# TM8_EVO_Dad.net
KiCad netlist of a schematic drawn in EAGLE
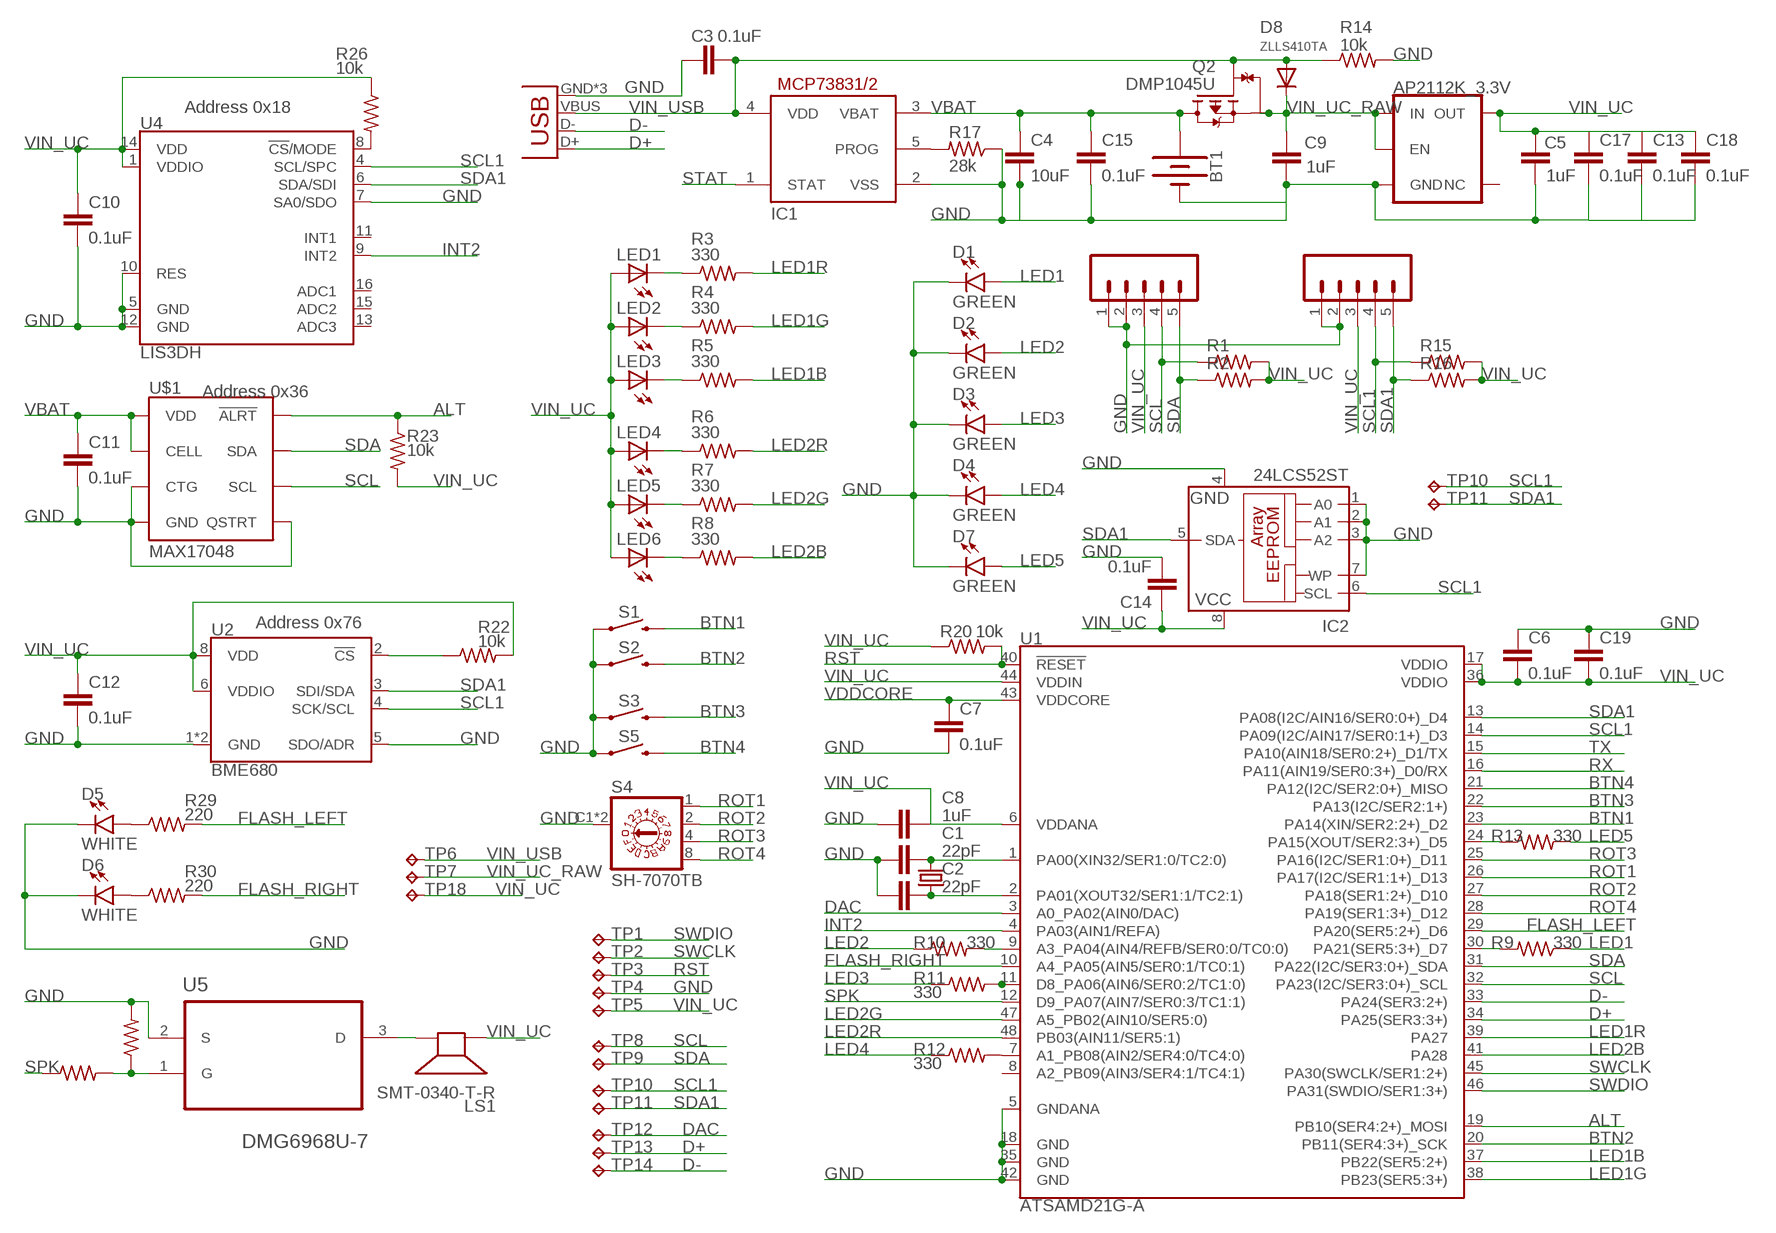
[diagram p0: schematic, sheet 1]

(export (version "E")
  (design (tool "Eeschema 10.0.6"))
  (components
    (comp (ref "AP2112K_3.3V")
      (value "3.3V")
      (footprint "eagle-import:SOT23-5")
      (libsource (lib "eagle-import") (part "V_REG_AP2112K-3.3V"))
    )
    (comp (ref "BT1")
      (value "BATTERY-20MM_SMD_4LEGS_OVERPASTE_INNER")
      (footprint "eagle-import:BATTCON_20MM_4LEGS_OVERPASTE_INNER")
      (libsource (lib "eagle-import") (part "BATTERY-20MM_SMD_4LEGS_OVERPASTE_INNER"))
    )
    (comp (ref "C1")
      (value "22pF")
      (footprint "eagle-import:C0402")
      (libsource (lib "eagle-import") (part "C-EUC0402"))
    )
    (comp (ref "C2")
      (value "22pF")
      (footprint "eagle-import:C0402")
      (libsource (lib "eagle-import") (part "C-EUC0402"))
    )
    (comp (ref "C3")
      (value "0.1uF")
      (footprint "eagle-import:C0402")
      (libsource (lib "eagle-import") (part "C-EUC0402"))
    )
    (comp (ref "C4")
      (value "10uF")
      (footprint "eagle-import:C0402")
      (libsource (lib "eagle-import") (part "C-EUC0402"))
    )
    (comp (ref "C5")
      (value "1uF")
      (footprint "eagle-import:C0402")
      (libsource (lib "eagle-import") (part "C-EUC0402"))
    )
    (comp (ref "C6")
      (value "0.1uF")
      (footprint "eagle-import:C0402")
      (libsource (lib "eagle-import") (part "C-EUC0402"))
    )
    (comp (ref "C7")
      (value "0.1uF")
      (footprint "eagle-import:C0402")
      (libsource (lib "eagle-import") (part "C-EUC0402"))
    )
    (comp (ref "C8")
      (value "1uF")
      (footprint "eagle-import:C0402")
      (libsource (lib "eagle-import") (part "C-EUC0402"))
    )
    (comp (ref "C9")
      (value "1uF")
      (footprint "eagle-import:C0402")
      (libsource (lib "eagle-import") (part "C-EUC0402"))
    )
    (comp (ref "C10")
      (value "0.1uF")
      (footprint "eagle-import:C0402")
      (libsource (lib "eagle-import") (part "C-EUC0402"))
    )
    (comp (ref "C11")
      (value "0.1uF")
      (footprint "eagle-import:C0402")
      (libsource (lib "eagle-import") (part "C-EUC0402"))
    )
    (comp (ref "C12")
      (value "0.1uF")
      (footprint "eagle-import:C0402")
      (libsource (lib "eagle-import") (part "C-EUC0402"))
    )
    (comp (ref "C13")
      (value "0.1uF")
      (footprint "eagle-import:C0402")
      (libsource (lib "eagle-import") (part "C-EUC0402"))
    )
    (comp (ref "C14")
      (value "0.1uF")
      (footprint "eagle-import:C0402")
      (libsource (lib "eagle-import") (part "C-EUC0402"))
    )
    (comp (ref "C15")
      (value "0.1uF")
      (footprint "eagle-import:C0402")
      (libsource (lib "eagle-import") (part "C-EUC0402"))
    )
    (comp (ref "C17")
      (value "0.1uF")
      (footprint "eagle-import:C0402")
      (libsource (lib "eagle-import") (part "C-EUC0402"))
    )
    (comp (ref "C18")
      (value "0.1uF")
      (footprint "eagle-import:C0402")
      (libsource (lib "eagle-import") (part "C-EUC0402"))
    )
    (comp (ref "C19")
      (value "0.1uF")
      (footprint "eagle-import:C0402")
      (libsource (lib "eagle-import") (part "C-EUC0402"))
    )
    (comp (ref "D1")
      (value "GREEN")
      (footprint "eagle-import:LED-1206")
      (libsource (lib "eagle-import") (part "LED-GREEN1206"))
    )
    (comp (ref "D2")
      (value "GREEN")
      (footprint "eagle-import:LED-1206")
      (libsource (lib "eagle-import") (part "LED-GREEN1206"))
    )
    (comp (ref "D3")
      (value "GREEN")
      (footprint "eagle-import:LED-1206")
      (libsource (lib "eagle-import") (part "LED-GREEN1206"))
    )
    (comp (ref "D4")
      (value "GREEN")
      (footprint "eagle-import:LED-1206")
      (libsource (lib "eagle-import") (part "LED-GREEN1206"))
    )
    (comp (ref "D5")
      (value "WHITE")
      (footprint "eagle-import:LED-1206")
      (libsource (lib "eagle-import") (part "LED-WHITE1206"))
    )
    (comp (ref "D6")
      (value "WHITE")
      (footprint "eagle-import:LED-1206")
      (libsource (lib "eagle-import") (part "LED-WHITE1206"))
    )
    (comp (ref "D7")
      (value "GREEN")
      (footprint "eagle-import:LED-1206")
      (libsource (lib "eagle-import") (part "LED-GREEN1206"))
    )
    (comp (ref "D8")
      (value "ZLLS410TA")
      (footprint "eagle-import:SOD-323F")
      (libsource (lib "eagle-import") (part "DIODESOD-323F"))
    )
    (comp (ref "IC1")
      (value "MCP73831/OT")
      (footprint "eagle-import:SOT23-5L")
      (libsource (lib "eagle-import") (part "MCP73831/OT"))
    )
    (comp (ref "IC2")
      (value "24LCS52ST")
      (footprint "eagle-import:TSSOP8")
      (fields (field (name "MF") "MICROCHIP") (field (name "MPN") "24LCS52T/ST"))
      (libsource (lib "eagle-import") (part "24STLCS52"))
    )
    (comp (ref "JP2")
      (value "USB-MICROB")
      (footprint "eagle-import:USB-MICROB")
      (libsource (lib "eagle-import") (part "USB-MICROB"))
    )
    (comp (ref "LCD1")
      (value "CONN_05VERT_FEMALE_HEADER")
      (footprint "eagle-import:1X05_SMD_VERTICAL_COMBO")
      (libsource (lib "eagle-import") (part "CONN_05VERT_FEMALE_HEADER"))
    )
    (comp (ref "LCD2")
      (value "CONN_05VERT_FEMALE_HEADER")
      (footprint "eagle-import:1X05_SMD_VERTICAL_COMBO")
      (libsource (lib "eagle-import") (part "CONN_05VERT_FEMALE_HEADER"))
    )
    (comp (ref "LED1")
      (value "LEDCHIPLED_0805")
      (footprint "eagle-import:CHIPLED_0805")
      (libsource (lib "eagle-import") (part "LEDCHIPLED_0805"))
    )
    (comp (ref "LED2")
      (value "LEDCHIPLED_0805")
      (footprint "eagle-import:CHIPLED_0805")
      (libsource (lib "eagle-import") (part "LEDCHIPLED_0805"))
    )
    (comp (ref "LED3")
      (value "LEDCHIPLED_0805")
      (footprint "eagle-import:CHIPLED_0805")
      (libsource (lib "eagle-import") (part "LEDCHIPLED_0805"))
    )
    (comp (ref "LED4")
      (value "LEDCHIPLED_0805")
      (footprint "eagle-import:CHIPLED_0805")
      (libsource (lib "eagle-import") (part "LEDCHIPLED_0805"))
    )
    (comp (ref "LED5")
      (value "LEDCHIPLED_0805")
      (footprint "eagle-import:CHIPLED_0805")
      (libsource (lib "eagle-import") (part "LEDCHIPLED_0805"))
    )
    (comp (ref "LED6")
      (value "LEDCHIPLED_0805")
      (footprint "eagle-import:CHIPLED_0805")
      (libsource (lib "eagle-import") (part "LEDCHIPLED_0805"))
    )
    (comp (ref "LS1")
      (value "SMT-0340-T-R")
      (footprint "eagle-import:XDCR_SMT-0340-T-R")
      (fields (field (name "MANUFACTURER") "Pui Audio"))
      (libsource (lib "eagle-import") (part "SMT-0340-T-R"))
    )
    (comp (ref "Q2")
      (value "DMP1045U")
      (footprint "eagle-import:SOT91P240X110-3N")
      (fields (field (name "MF") "Diodes Inc."))
      (libsource (lib "eagle-import") (part "DMP1045U"))
    )
    (comp (ref "R1")
      (value "R-US_R0402")
      (footprint "eagle-import:R0402")
      (libsource (lib "eagle-import") (part "adafruit_25768682_R-US_R0402"))
    )
    (comp (ref "R2")
      (value "R-US_R0402")
      (footprint "eagle-import:R0402")
      (libsource (lib "eagle-import") (part "adafruit_25768682_R-US_R0402"))
    )
    (comp (ref "R3")
      (value "330")
      (footprint "eagle-import:R0402")
      (libsource (lib "eagle-import") (part "rcl_334_R-US_R0402"))
    )
    (comp (ref "R4")
      (value "330")
      (footprint "eagle-import:R0402")
      (libsource (lib "eagle-import") (part "rcl_334_R-US_R0402"))
    )
    (comp (ref "R5")
      (value "330")
      (footprint "eagle-import:R0402")
      (libsource (lib "eagle-import") (part "rcl_334_R-US_R0402"))
    )
    (comp (ref "R6")
      (value "330")
      (footprint "eagle-import:R0402")
      (libsource (lib "eagle-import") (part "rcl_334_R-US_R0402"))
    )
    (comp (ref "R7")
      (value "330")
      (footprint "eagle-import:R0402")
      (libsource (lib "eagle-import") (part "rcl_334_R-US_R0402"))
    )
    (comp (ref "R8")
      (value "330")
      (footprint "eagle-import:R0402")
      (libsource (lib "eagle-import") (part "rcl_334_R-US_R0402"))
    )
    (comp (ref "R9")
      (value "330")
      (footprint "eagle-import:R0402")
      (libsource (lib "eagle-import") (part "rcl_334_R-US_R0402"))
    )
    (comp (ref "R10")
      (value "330")
      (footprint "eagle-import:R0402")
      (libsource (lib "eagle-import") (part "rcl_334_R-US_R0402"))
    )
    (comp (ref "R11")
      (value "330")
      (footprint "eagle-import:R0402")
      (libsource (lib "eagle-import") (part "rcl_334_R-US_R0402"))
    )
    (comp (ref "R12")
      (value "330")
      (footprint "eagle-import:R0402")
      (libsource (lib "eagle-import") (part "rcl_334_R-US_R0402"))
    )
    (comp (ref "R13")
      (value "330")
      (footprint "eagle-import:R0402")
      (libsource (lib "eagle-import") (part "rcl_334_R-US_R0402"))
    )
    (comp (ref "R14")
      (value "10k")
      (footprint "eagle-import:R0402")
      (libsource (lib "eagle-import") (part "R-US_R0402"))
    )
    (comp (ref "R15")
      (value "R-US_R0402")
      (footprint "eagle-import:R0402")
      (libsource (lib "eagle-import") (part "adafruit_25768682_R-US_R0402"))
    )
    (comp (ref "R16")
      (value "R-US_R0402")
      (footprint "eagle-import:R0402")
      (libsource (lib "eagle-import") (part "adafruit_25768682_R-US_R0402"))
    )
    (comp (ref "R17")
      (value "28k")
      (footprint "eagle-import:R0402")
      (libsource (lib "eagle-import") (part "adafruit_25768682_R-US_R0402"))
    )
    (comp (ref "R18")
      (value "220")
      (footprint "eagle-import:R0402")
      (libsource (lib "eagle-import") (part "rcl_334_R-US_R0402"))
    )
    (comp (ref "R19")
      (value "220")
      (footprint "eagle-import:R0402")
      (libsource (lib "eagle-import") (part "rcl_334_R-US_R0402"))
    )
    (comp (ref "R20")
      (value "10k")
      (footprint "eagle-import:R0402")
      (libsource (lib "eagle-import") (part "adafruit_25768682_R-US_R0402"))
    )
    (comp (ref "R22")
      (value "10k")
      (footprint "eagle-import:R0402")
      (libsource (lib "eagle-import") (part "rcl_334_R-US_R0402"))
    )
    (comp (ref "R23")
      (value "10k")
      (footprint "eagle-import:R0402")
      (libsource (lib "eagle-import") (part "rcl_334_R-US_R0402"))
    )
    (comp (ref "R26")
      (value "10k")
      (footprint "eagle-import:R0402")
      (libsource (lib "eagle-import") (part "rcl_334_R-US_R0402"))
    )
    (comp (ref "R29")
      (value "220")
      (footprint "eagle-import:R0402")
      (libsource (lib "eagle-import") (part "rcl_334_R-US_R0402"))
    )
    (comp (ref "R30")
      (value "220")
      (footprint "eagle-import:R0402")
      (libsource (lib "eagle-import") (part "rcl_334_R-US_R0402"))
    )
    (comp (ref "S1")
      (value "MOMENTARY-SWITCH-SPST-SMD-6.0X3.5MM")
      (footprint "eagle-import:TACTILE_SWITCH_SMD_6.0X3.5MM")
      (libsource (lib "eagle-import") (part "MOMENTARY-SWITCH-SPST-SMD-6.0X3.5MM"))
    )
    (comp (ref "S2")
      (value "MOMENTARY-SWITCH-SPST-SMD-6.0X3.5MM")
      (footprint "eagle-import:TACTILE_SWITCH_SMD_6.0X3.5MM")
      (libsource (lib "eagle-import") (part "MOMENTARY-SWITCH-SPST-SMD-6.0X3.5MM"))
    )
    (comp (ref "S3")
      (value "MOMENTARY-SWITCH-SPST-SMD-6.0X3.5MM")
      (footprint "eagle-import:TACTILE_SWITCH_SMD_6.0X3.5MM")
      (libsource (lib "eagle-import") (part "MOMENTARY-SWITCH-SPST-SMD-6.0X3.5MM"))
    )
    (comp (ref "S4")
      (value "SH-7070TB")
      (footprint "eagle-import:SH-7070B")
      (fields (field (name "MF") "Nidec Copal"))
      (libsource (lib "eagle-import") (part "SH-7070TB"))
    )
    (comp (ref "S5")
      (value "MOMENTARY-SWITCH-SPST-SMD-6.0X3.5MM")
      (footprint "eagle-import:TACTILE_SWITCH_SMD_6.0X3.5MM")
      (libsource (lib "eagle-import") (part "MOMENTARY-SWITCH-SPST-SMD-6.0X3.5MM"))
    )
    (comp (ref "TP1")
      (value "TPTP14R")
      (footprint "eagle-import:TP14R")
      (libsource (lib "eagle-import") (part "TPTP14R"))
    )
    (comp (ref "TP2")
      (value "TPTP14R")
      (footprint "eagle-import:TP14R")
      (libsource (lib "eagle-import") (part "TPTP14R"))
    )
    (comp (ref "TP3")
      (value "TPTP14R")
      (footprint "eagle-import:TP14R")
      (libsource (lib "eagle-import") (part "TPTP14R"))
    )
    (comp (ref "TP4")
      (value "TPTP14R")
      (footprint "eagle-import:TP14R")
      (libsource (lib "eagle-import") (part "TPTP14R"))
    )
    (comp (ref "TP5")
      (value "TPTP14R")
      (footprint "eagle-import:TP14R")
      (libsource (lib "eagle-import") (part "TPTP14R"))
    )
    (comp (ref "TP6")
      (value "TPTP14R")
      (footprint "eagle-import:TP14R")
      (libsource (lib "eagle-import") (part "TPTP14R"))
    )
    (comp (ref "TP7")
      (value "TPTP14R")
      (footprint "eagle-import:TP14R")
      (libsource (lib "eagle-import") (part "TPTP14R"))
    )
    (comp (ref "TP8")
      (value "TPTP14R")
      (footprint "eagle-import:TP14R")
      (libsource (lib "eagle-import") (part "TPTP14R"))
    )
    (comp (ref "TP9")
      (value "TPTP14R")
      (footprint "eagle-import:TP14R")
      (libsource (lib "eagle-import") (part "TPTP14R"))
    )
    (comp (ref "TP10")
      (value "TPTP14R")
      (footprint "eagle-import:TP14R")
      (libsource (lib "eagle-import") (part "TPTP14R"))
    )
    (comp (ref "TP11")
      (value "TPTP14R")
      (footprint "eagle-import:TP14R")
      (libsource (lib "eagle-import") (part "TPTP14R"))
    )
    (comp (ref "TP12")
      (value "TPTP14R")
      (footprint "eagle-import:TP14R")
      (libsource (lib "eagle-import") (part "TPTP14R"))
    )
    (comp (ref "TP13")
      (value "TPTP14R")
      (footprint "eagle-import:TP14R")
      (libsource (lib "eagle-import") (part "TPTP14R"))
    )
    (comp (ref "TP14")
      (value "TPTP14R")
      (footprint "eagle-import:TP14R")
      (libsource (lib "eagle-import") (part "TPTP14R"))
    )
    (comp (ref "TP15")
      (value "TPTP14R")
      (footprint "eagle-import:TP14R")
      (libsource (lib "eagle-import") (part "TPTP14R"))
    )
    (comp (ref "TP16")
      (value "TPTP14R")
      (footprint "eagle-import:TP14R")
      (libsource (lib "eagle-import") (part "TPTP14R"))
    )
    (comp (ref "TP18")
      (value "TPTP14R")
      (footprint "eagle-import:TP14R")
      (libsource (lib "eagle-import") (part "TPTP14R"))
    )
    (comp (ref "U$1")
      (value "MAX17048")
      (footprint "eagle-import:DFN-8")
      (libsource (lib "eagle-import") (part "MAX17048DFN8"))
    )
    (comp (ref "U1")
      (value "ATSAMD21G-A")
      (footprint "eagle-import:TQFP-48")
      (libsource (lib "eagle-import") (part "ATSAMD21G-A"))
    )
    (comp (ref "U2")
      (value "BME680")
      (footprint "eagle-import:LGA3.0X3.0")
      (libsource (lib "eagle-import") (part "BME680-LGA"))
    )
    (comp (ref "U4")
      (value "LIS3DH")
      (footprint "eagle-import:LGA-16-3X3")
      (libsource (lib "eagle-import") (part "LIS3DH"))
    )
    (comp (ref "U5")
      (value "DMG6968U-7")
      (footprint "eagle-import:SOT95P240X110-3N")
      (fields (field (name "MF") "Diodes Inc."))
      (libsource (lib "eagle-import") (part "DMG6968U-7"))
    )
    (comp (ref "Y1")
      (value "32.768kHz")
      (footprint "eagle-import:CRYSTAL-SMD-3.2X1.5MM")
      (libsource (lib "eagle-import") (part "CRYSTAL-32.768KHZSMD-3.2X1.5"))
    )
  )
  (nets
    (net (code "1") (name "/ALT") (class "Default")
      (node (ref "R23") (pin "1") (pinfunction "1_1") (pintype "passive"))
      (node (ref "U$1") (pin "P$5") (pinfunction "~{ALRT}_P$5") (pintype "bidirectional"))
      (node (ref "U1") (pin "19") (pinfunction "PB10(SER4:2+)_MOSI_19") (pintype "bidirectional"))
    )
    (net (code "2") (name "/BTN1") (class "Default")
      (node (ref "S1") (pin "2") (pinfunction "2_2") (pintype "passive"))
      (node (ref "U1") (pin "23") (pinfunction "PA14(XIN/SER2:2+)_D2_23") (pintype "bidirectional"))
    )
    (net (code "3") (name "/BTN2") (class "Default")
      (node (ref "S2") (pin "2") (pinfunction "2_2") (pintype "passive"))
      (node (ref "U1") (pin "20") (pinfunction "PB11(SER4:3+)_SCK_20") (pintype "bidirectional"))
    )
    (net (code "4") (name "/BTN3") (class "Default")
      (node (ref "S3") (pin "2") (pinfunction "2_2") (pintype "passive"))
      (node (ref "U1") (pin "22") (pinfunction "PA13(I2C/SER2:1+)_22") (pintype "bidirectional"))
    )
    (net (code "5") (name "/BTN4") (class "Default")
      (node (ref "S5") (pin "2") (pinfunction "2_2") (pintype "passive"))
      (node (ref "U1") (pin "21") (pinfunction "PA12(I2C/SER2:0+)_MISO_21") (pintype "bidirectional"))
    )
    (net (code "6") (name "/D+") (class "Default")
      (node (ref "JP2") (pin "D+") (pinfunction "D+_D+") (pintype "bidirectional"))
      (node (ref "TP13") (pin "TP") (pinfunction "TP_TP") (pintype "input"))
      (node (ref "U1") (pin "34") (pinfunction "PA25(SER3:3+)_34") (pintype "bidirectional"))
    )
    (net (code "7") (name "/D-") (class "Default")
      (node (ref "JP2") (pin "D-") (pinfunction "D-_D-") (pintype "bidirectional"))
      (node (ref "TP14") (pin "TP") (pinfunction "TP_TP") (pintype "input"))
      (node (ref "U1") (pin "33") (pinfunction "PA24(SER3:2+)_33") (pintype "bidirectional"))
    )
    (net (code "8") (name "/DAC") (class "Default")
      (node (ref "TP12") (pin "TP") (pinfunction "TP_TP") (pintype "input"))
      (node (ref "U1") (pin "3") (pinfunction "A0_PA02(AIN0/DAC)_3") (pintype "bidirectional"))
    )
    (net (code "9") (name "/FLASH_LEFT") (class "Default")
      (node (ref "R29") (pin "2") (pinfunction "2_2") (pintype "passive"))
      (node (ref "U1") (pin "29") (pinfunction "PA20(SER5:2+)_D6_29") (pintype "bidirectional"))
    )
    (net (code "10") (name "/FLASH_RIGHT") (class "Default")
      (node (ref "R30") (pin "2") (pinfunction "2_2") (pintype "passive"))
      (node (ref "U1") (pin "10") (pinfunction "A4_PA05(AIN5/SER0:1/TC0:1)_10") (pintype "bidirectional"))
    )
    (net (code "11") (name "/GND") (class "Default")
      (node (ref "AP2112K_3.3V") (pin "2") (pinfunction "GND_2") (pintype "input"))
      (node (ref "BT1") (pin "2") (pinfunction "-_2") (pintype "power_in"))
      (node (ref "C1") (pin "1") (pinfunction "1_1") (pintype "passive"))
      (node (ref "C10") (pin "2") (pinfunction "2_2") (pintype "passive"))
      (node (ref "C11") (pin "2") (pinfunction "2_2") (pintype "passive"))
      (node (ref "C12") (pin "2") (pinfunction "2_2") (pintype "passive"))
      (node (ref "C13") (pin "2") (pinfunction "2_2") (pintype "passive"))
      (node (ref "C14") (pin "2") (pinfunction "2_2") (pintype "passive"))
      (node (ref "C15") (pin "2") (pinfunction "2_2") (pintype "passive"))
      (node (ref "C17") (pin "2") (pinfunction "2_2") (pintype "passive"))
      (node (ref "C18") (pin "2") (pinfunction "2_2") (pintype "passive"))
      (node (ref "C19") (pin "1") (pinfunction "1_1") (pintype "passive"))
      (node (ref "C2") (pin "1") (pinfunction "1_1") (pintype "passive"))
      (node (ref "C3") (pin "1") (pinfunction "1_1") (pintype "passive"))
      (node (ref "C4") (pin "2") (pinfunction "2_2") (pintype "passive"))
      (node (ref "C5") (pin "2") (pinfunction "2_2") (pintype "passive"))
      (node (ref "C6") (pin "1") (pinfunction "1_1") (pintype "passive"))
      (node (ref "C7") (pin "2") (pinfunction "2_2") (pintype "passive"))
      (node (ref "C8") (pin "1") (pinfunction "1_1") (pintype "passive"))
      (node (ref "C9") (pin "2") (pinfunction "2_2") (pintype "passive"))
      (node (ref "D1") (pin "C") (pinfunction "C_C") (pintype "passive"))
      (node (ref "D2") (pin "C") (pinfunction "C_C") (pintype "passive"))
      (node (ref "D3") (pin "C") (pinfunction "C_C") (pintype "passive"))
      (node (ref "D4") (pin "C") (pinfunction "C_C") (pintype "passive"))
      (node (ref "D5") (pin "C") (pinfunction "C_C") (pintype "passive"))
      (node (ref "D6") (pin "C") (pinfunction "C_C") (pintype "passive"))
      (node (ref "D7") (pin "C") (pinfunction "C_C") (pintype "passive"))
      (node (ref "IC1") (pin "2") (pinfunction "VSS_2") (pintype "power_in"))
      (node (ref "IC2") (pin "1") (pinfunction "A0_1") (pintype "input"))
      (node (ref "IC2") (pin "2") (pinfunction "A1_2") (pintype "input"))
      (node (ref "IC2") (pin "3") (pinfunction "A2_3") (pintype "input"))
      (node (ref "IC2") (pin "4") (pinfunction "GND_4") (pintype "power_in"))
      (node (ref "IC2") (pin "7") (pinfunction "WP_7") (pintype "input"))
      (node (ref "JP2") (pin "GND") (pinfunction "GND_GND") (pintype "bidirectional"))
      (node (ref "JP2") (pin "MT1") (pinfunction "GND_MT1") (pintype "bidirectional"))
      (node (ref "JP2") (pin "MT2") (pinfunction "GND_MT2") (pintype "bidirectional"))
      (node (ref "LCD1") (pin "1") (pinfunction "1_1") (pintype "passive"))
      (node (ref "LCD1") (pin "2") (pinfunction "2_2") (pintype "passive"))
      (node (ref "LCD2") (pin "1") (pinfunction "1_1") (pintype "passive"))
      (node (ref "LCD2") (pin "2") (pinfunction "2_2") (pintype "passive"))
      (node (ref "R14") (pin "2") (pinfunction "2_2") (pintype "passive"))
      (node (ref "R17") (pin "1") (pinfunction "1_1") (pintype "passive"))
      (node (ref "R19") (pin "2") (pinfunction "2_2") (pintype "passive"))
      (node (ref "S1") (pin "1") (pinfunction "1_1") (pintype "passive"))
      (node (ref "S2") (pin "1") (pinfunction "1_1") (pintype "passive"))
      (node (ref "S3") (pin "1") (pinfunction "1_1") (pintype "passive"))
      (node (ref "S4") (pin "C1") (pinfunction "C_C1") (pintype "passive"))
      (node (ref "S4") (pin "C2") (pinfunction "C_C2") (pintype "passive"))
      (node (ref "S5") (pin "1") (pinfunction "1_1") (pintype "passive"))
      (node (ref "TP4") (pin "TP") (pinfunction "TP_TP") (pintype "input"))
      (node (ref "U$1") (pin "P$1") (pinfunction "CTG_P$1") (pintype "input"))
      (node (ref "U$1") (pin "P$4") (pinfunction "GND_P$4") (pintype "bidirectional"))
      (node (ref "U$1") (pin "P$6") (pinfunction "QSTRT_P$6") (pintype "bidirectional"))
      (node (ref "U$1") (pin "P$9") (pinfunction "GND_P$9") (pintype "bidirectional"))
      (node (ref "U1") (pin "18") (pinfunction "GND_18") (pintype "bidirectional"))
      (node (ref "U1") (pin "35") (pinfunction "GND_35") (pintype "bidirectional"))
      (node (ref "U1") (pin "42") (pinfunction "GND_42") (pintype "bidirectional"))
      (node (ref "U1") (pin "5") (pinfunction "GNDANA_5") (pintype "bidirectional"))
      (node (ref "U2") (pin "1") (pinfunction "GND_1") (pintype "bidirectional"))
      (node (ref "U2") (pin "5") (pinfunction "SDO/ADR_5") (pintype "bidirectional"))
      (node (ref "U2") (pin "7") (pinfunction "GND_7") (pintype "bidirectional"))
      (node (ref "U4") (pin "10") (pinfunction "RES_10") (pintype "bidirectional"))
      (node (ref "U4") (pin "12") (pinfunction "GND_12") (pintype "bidirectional"))
      (node (ref "U4") (pin "5") (pinfunction "GND_5") (pintype "bidirectional"))
      (node (ref "U4") (pin "7") (pinfunction "SA0/SDO_7") (pintype "bidirectional"))
      (node (ref "U5") (pin "2") (pinfunction "S_2") (pintype "passive"))
    )
    (net (code "12") (name "/INT2") (class "Default")
      (node (ref "U1") (pin "4") (pinfunction "PA03(AIN1/REFA)_4") (pintype "bidirectional"))
      (node (ref "U4") (pin "9") (pinfunction "INT2_9") (pintype "bidirectional"))
    )
    (net (code "13") (name "/LED1") (class "Default")
      (node (ref "D1") (pin "A") (pinfunction "A_A") (pintype "passive"))
      (node (ref "R9") (pin "1") (pinfunction "1_1") (pintype "passive"))
    )
    (net (code "14") (name "/LED1B") (class "Default")
      (node (ref "R5") (pin "2") (pinfunction "2_2") (pintype "passive"))
      (node (ref "U1") (pin "37") (pinfunction "PB22(SER5:2+)_37") (pintype "bidirectional"))
    )
    (net (code "15") (name "/LED1G") (class "Default")
      (node (ref "R4") (pin "2") (pinfunction "2_2") (pintype "passive"))
      (node (ref "U1") (pin "38") (pinfunction "PB23(SER5:3+)_38") (pintype "bidirectional"))
    )
    (net (code "16") (name "/LED1R") (class "Default")
      (node (ref "R3") (pin "2") (pinfunction "2_2") (pintype "passive"))
      (node (ref "U1") (pin "39") (pinfunction "PA27_39") (pintype "bidirectional"))
    )
    (net (code "17") (name "/LED2") (class "Default")
      (node (ref "D2") (pin "A") (pinfunction "A_A") (pintype "passive"))
      (node (ref "R10") (pin "1") (pinfunction "1_1") (pintype "passive"))
    )
    (net (code "18") (name "/LED2B") (class "Default")
      (node (ref "R8") (pin "2") (pinfunction "2_2") (pintype "passive"))
      (node (ref "U1") (pin "41") (pinfunction "PA28_41") (pintype "bidirectional"))
    )
    (net (code "19") (name "/LED2G") (class "Default")
      (node (ref "R7") (pin "2") (pinfunction "2_2") (pintype "passive"))
      (node (ref "U1") (pin "47") (pinfunction "A5_PB02(AIN10/SER5:0)_47") (pintype "bidirectional"))
    )
    (net (code "20") (name "/LED2R") (class "Default")
      (node (ref "R6") (pin "2") (pinfunction "2_2") (pintype "passive"))
      (node (ref "U1") (pin "48") (pinfunction "PB03(AIN11/SER5:1)_48") (pintype "bidirectional"))
    )
    (net (code "21") (name "/LED3") (class "Default")
      (node (ref "D3") (pin "A") (pinfunction "A_A") (pintype "passive"))
      (node (ref "R11") (pin "1") (pinfunction "1_1") (pintype "passive"))
    )
    (net (code "22") (name "/LED4") (class "Default")
      (node (ref "D4") (pin "A") (pinfunction "A_A") (pintype "passive"))
      (node (ref "R12") (pin "1") (pinfunction "1_1") (pintype "passive"))
    )
    (net (code "23") (name "/LED5") (class "Default")
      (node (ref "D7") (pin "A") (pinfunction "A_A") (pintype "passive"))
      (node (ref "R13") (pin "2") (pinfunction "2_2") (pintype "passive"))
    )
    (net (code "24") (name "/ROT1") (class "Default")
      (node (ref "S4") (pin "1") (pinfunction "1_1") (pintype "passive"))
      (node (ref "U1") (pin "26") (pinfunction "PA17(I2C/SER1:1+)_D13_26") (pintype "bidirectional"))
    )
    (net (code "25") (name "/ROT2") (class "Default")
      (node (ref "S4") (pin "2") (pinfunction "2_2") (pintype "passive"))
      (node (ref "U1") (pin "27") (pinfunction "PA18(SER1:2+)_D10_27") (pintype "bidirectional"))
    )
    (net (code "26") (name "/ROT3") (class "Default")
      (node (ref "S4") (pin "4") (pinfunction "4_4") (pintype "passive"))
      (node (ref "U1") (pin "25") (pinfunction "PA16(I2C/SER1:0+)_D11_25") (pintype "bidirectional"))
    )
    (net (code "27") (name "/ROT4") (class "Default")
      (node (ref "S4") (pin "8") (pinfunction "8_8") (pintype "passive"))
      (node (ref "U1") (pin "28") (pinfunction "PA19(SER1:3+)_D12_28") (pintype "bidirectional"))
    )
    (net (code "28") (name "/RST") (class "Default")
      (node (ref "R20") (pin "2") (pinfunction "2_2") (pintype "passive"))
      (node (ref "TP3") (pin "TP") (pinfunction "TP_TP") (pintype "input"))
      (node (ref "U1") (pin "40") (pinfunction "~{RESET}_40") (pintype "bidirectional"))
    )
    (net (code "29") (name "/RX") (class "Default")
      (node (ref "U1") (pin "16") (pinfunction "PA11(AIN19/SER0:3+)_D0/RX_16") (pintype "bidirectional"))
    )
    (net (code "30") (name "/SCL") (class "Default")
      (node (ref "LCD1") (pin "4") (pinfunction "4_4") (pintype "passive"))
      (node (ref "R1") (pin "1") (pinfunction "1_1") (pintype "passive"))
      (node (ref "TP8") (pin "TP") (pinfunction "TP_TP") (pintype "input"))
      (node (ref "U$1") (pin "P$7") (pinfunction "SCL_P$7") (pintype "output"))
      (node (ref "U1") (pin "32") (pinfunction "PA23(I2C/SER3:0+)_SCL_32") (pintype "bidirectional"))
    )
    (net (code "31") (name "/SCL1") (class "Default")
      (node (ref "IC2") (pin "6") (pinfunction "SCL_6") (pintype "input"))
      (node (ref "LCD2") (pin "4") (pinfunction "4_4") (pintype "passive"))
      (node (ref "R15") (pin "1") (pinfunction "1_1") (pintype "passive"))
      (node (ref "TP10") (pin "TP") (pinfunction "TP_TP") (pintype "input"))
      (node (ref "TP15") (pin "TP") (pinfunction "TP_TP") (pintype "input"))
      (node (ref "U1") (pin "14") (pinfunction "PA09(I2C/AIN17/SER0:1+)_D3_14") (pintype "bidirectional"))
      (node (ref "U2") (pin "4") (pinfunction "SCK/SCL_4") (pintype "bidirectional"))
      (node (ref "U4") (pin "4") (pinfunction "SCL/SPC_4") (pintype "bidirectional"))
    )
    (net (code "32") (name "/SDA") (class "Default")
      (node (ref "LCD1") (pin "5") (pinfunction "5_5") (pintype "passive"))
      (node (ref "R2") (pin "1") (pinfunction "1_1") (pintype "passive"))
      (node (ref "TP9") (pin "TP") (pinfunction "TP_TP") (pintype "input"))
      (node (ref "U$1") (pin "P$8") (pinfunction "SDA_P$8") (pintype "input"))
      (node (ref "U1") (pin "31") (pinfunction "PA22(I2C/SER3:0+)_SDA_31") (pintype "bidirectional"))
    )
    (net (code "33") (name "/SDA1") (class "Default")
      (node (ref "IC2") (pin "5") (pinfunction "SDA_5") (pintype "bidirectional"))
      (node (ref "LCD2") (pin "5") (pinfunction "5_5") (pintype "passive"))
      (node (ref "R16") (pin "1") (pinfunction "1_1") (pintype "passive"))
      (node (ref "TP11") (pin "TP") (pinfunction "TP_TP") (pintype "input"))
      (node (ref "TP16") (pin "TP") (pinfunction "TP_TP") (pintype "input"))
      (node (ref "U1") (pin "13") (pinfunction "PA08(I2C/AIN16/SER0:0+)_D4_13") (pintype "bidirectional"))
      (node (ref "U2") (pin "3") (pinfunction "SDI/SDA_3") (pintype "bidirectional"))
      (node (ref "U4") (pin "6") (pinfunction "SDA/SDI_6") (pintype "bidirectional"))
    )
    (net (code "34") (name "/SPK") (class "Default")
      (node (ref "R18") (pin "1") (pinfunction "1_1") (pintype "passive"))
      (node (ref "U1") (pin "12") (pinfunction "D9_PA07(AIN7/SER0:3/TC1:1)_12") (pintype "bidirectional"))
    )
    (net (code "35") (name "/STAT") (class "Default")
      (node (ref "IC1") (pin "1") (pinfunction "STAT_1") (pintype "output"))
    )
    (net (code "36") (name "/SWCLK") (class "Default")
      (node (ref "TP2") (pin "TP") (pinfunction "TP_TP") (pintype "input"))
      (node (ref "U1") (pin "45") (pinfunction "PA30(SWCLK/SER1:2+)_45") (pintype "bidirectional"))
    )
    (net (code "37") (name "/SWDIO") (class "Default")
      (node (ref "TP1") (pin "TP") (pinfunction "TP_TP") (pintype "input"))
      (node (ref "U1") (pin "46") (pinfunction "PA31(SWDIO/SER1:3+)_46") (pintype "bidirectional"))
    )
    (net (code "38") (name "/TX") (class "Default")
      (node (ref "U1") (pin "15") (pinfunction "PA10(AIN18/SER0:2+)_D1/TX_15") (pintype "bidirectional"))
    )
    (net (code "39") (name "/VBAT") (class "Default")
      (node (ref "BT1") (pin "1") (pinfunction "+_1") (pintype "power_in"))
      (node (ref "C11") (pin "1") (pinfunction "1_1") (pintype "passive"))
      (node (ref "C15") (pin "1") (pinfunction "1_1") (pintype "passive"))
      (node (ref "C4") (pin "1") (pinfunction "1_1") (pintype "passive"))
      (node (ref "IC1") (pin "3") (pinfunction "VBAT_3") (pintype "bidirectional"))
      (node (ref "Q2") (pin "3") (pinfunction "D_3") (pintype "passive"))
      (node (ref "U$1") (pin "P$2") (pinfunction "CELL_P$2") (pintype "input"))
      (node (ref "U$1") (pin "P$3") (pinfunction "VDD_P$3") (pintype "bidirectional"))
    )
    (net (code "40") (name "/VDDCORE") (class "Default")
      (node (ref "C7") (pin "1") (pinfunction "1_1") (pintype "passive"))
      (node (ref "U1") (pin "43") (pinfunction "VDDCORE_43") (pintype "bidirectional"))
    )
    (net (code "41") (name "/VIN_UC") (class "Default")
      (node (ref "AP2112K_3.3V") (pin "5") (pinfunction "OUT_5") (pintype "passive"))
      (node (ref "C10") (pin "1") (pinfunction "1_1") (pintype "passive"))
      (node (ref "C12") (pin "1") (pinfunction "1_1") (pintype "passive"))
      (node (ref "C13") (pin "1") (pinfunction "1_1") (pintype "passive"))
      (node (ref "C14") (pin "1") (pinfunction "1_1") (pintype "passive"))
      (node (ref "C17") (pin "1") (pinfunction "1_1") (pintype "passive"))
      (node (ref "C18") (pin "1") (pinfunction "1_1") (pintype "passive"))
      (node (ref "C19") (pin "2") (pinfunction "2_2") (pintype "passive"))
      (node (ref "C5") (pin "1") (pinfunction "1_1") (pintype "passive"))
      (node (ref "C6") (pin "2") (pinfunction "2_2") (pintype "passive"))
      (node (ref "C8") (pin "2") (pinfunction "2_2") (pintype "passive"))
      (node (ref "IC2") (pin "8") (pinfunction "VCC_8") (pintype "power_in"))
      (node (ref "LCD1") (pin "3") (pinfunction "3_3") (pintype "passive"))
      (node (ref "LCD2") (pin "3") (pinfunction "3_3") (pintype "passive"))
      (node (ref "LED1") (pin "A") (pinfunction "A_A") (pintype "passive"))
      (node (ref "LED2") (pin "A") (pinfunction "A_A") (pintype "passive"))
      (node (ref "LED3") (pin "A") (pinfunction "A_A") (pintype "passive"))
      (node (ref "LED4") (pin "A") (pinfunction "A_A") (pintype "passive"))
      (node (ref "LED5") (pin "A") (pinfunction "A_A") (pintype "passive"))
      (node (ref "LED6") (pin "A") (pinfunction "A_A") (pintype "passive"))
      (node (ref "LS1") (pin "P") (pinfunction "P_P") (pintype "passive"))
      (node (ref "R1") (pin "2") (pinfunction "2_2") (pintype "passive"))
      (node (ref "R15") (pin "2") (pinfunction "2_2") (pintype "passive"))
      (node (ref "R16") (pin "2") (pinfunction "2_2") (pintype "passive"))
      (node (ref "R2") (pin "2") (pinfunction "2_2") (pintype "passive"))
      (node (ref "R20") (pin "1") (pinfunction "1_1") (pintype "passive"))
      (node (ref "R22") (pin "2") (pinfunction "2_2") (pintype "passive"))
      (node (ref "R23") (pin "2") (pinfunction "2_2") (pintype "passive"))
      (node (ref "R26") (pin "1") (pinfunction "1_1") (pintype "passive"))
      (node (ref "TP18") (pin "TP") (pinfunction "TP_TP") (pintype "input"))
      (node (ref "TP5") (pin "TP") (pinfunction "TP_TP") (pintype "input"))
      (node (ref "U1") (pin "17") (pinfunction "VDDIO_17") (pintype "bidirectional"))
      (node (ref "U1") (pin "36") (pinfunction "VDDIO_36") (pintype "bidirectional"))
      (node (ref "U1") (pin "44") (pinfunction "VDDIN_44") (pintype "bidirectional"))
      (node (ref "U1") (pin "6") (pinfunction "VDDANA_6") (pintype "bidirectional"))
      (node (ref "U2") (pin "6") (pinfunction "VDDIO_6") (pintype "bidirectional"))
      (node (ref "U2") (pin "8") (pinfunction "VDD_8") (pintype "bidirectional"))
      (node (ref "U4") (pin "1") (pinfunction "VDDIO_1") (pintype "bidirectional"))
      (node (ref "U4") (pin "14") (pinfunction "VDD_14") (pintype "bidirectional"))
    )
    (net (code "42") (name "/VIN_UC_RAW") (class "Default")
      (node (ref "AP2112K_3.3V") (pin "1") (pinfunction "IN_1") (pintype "input"))
      (node (ref "AP2112K_3.3V") (pin "3") (pinfunction "EN_3") (pintype "input"))
      (node (ref "C9") (pin "1") (pinfunction "1_1") (pintype "passive"))
      (node (ref "D8") (pin "C") (pinfunction "C_C") (pintype "passive"))
      (node (ref "Q2") (pin "2") (pinfunction "S_2") (pintype "passive"))
      (node (ref "TP7") (pin "TP") (pinfunction "TP_TP") (pintype "input"))
    )
    (net (code "43") (name "/VIN_USB") (class "Default")
      (node (ref "C3") (pin "2") (pinfunction "2_2") (pintype "passive"))
      (node (ref "D8") (pin "A") (pinfunction "A_A") (pintype "passive"))
      (node (ref "IC1") (pin "4") (pinfunction "VDD_4") (pintype "power_in"))
      (node (ref "JP2") (pin "VBUS") (pinfunction "VBUS_VBUS") (pintype "bidirectional"))
      (node (ref "Q2") (pin "1") (pinfunction "G_1") (pintype "passive"))
      (node (ref "R14") (pin "1") (pinfunction "1_1") (pintype "passive"))
      (node (ref "TP6") (pin "TP") (pinfunction "TP_TP") (pintype "input"))
    )
    (net (code "44") (name "Net-(D5-PadA)") (class "Default")
      (node (ref "D5") (pin "A") (pinfunction "A_A") (pintype "passive"))
      (node (ref "R29") (pin "1") (pinfunction "1_1") (pintype "passive"))
    )
    (net (code "45") (name "Net-(D6-PadA)") (class "Default")
      (node (ref "D6") (pin "A") (pinfunction "A_A") (pintype "passive"))
      (node (ref "R30") (pin "1") (pinfunction "1_1") (pintype "passive"))
    )
    (net (code "46") (name "Net-(IC1-PROG)") (class "Default")
      (node (ref "IC1") (pin "5") (pinfunction "PROG_5") (pintype "input"))
      (node (ref "R17") (pin "2") (pinfunction "2_2") (pintype "passive"))
    )
    (net (code "47") (name "Net-(LED1-PadC)") (class "Default")
      (node (ref "LED1") (pin "C") (pinfunction "C_C") (pintype "passive"))
      (node (ref "R3") (pin "1") (pinfunction "1_1") (pintype "passive"))
    )
    (net (code "48") (name "Net-(LED2-PadC)") (class "Default")
      (node (ref "LED2") (pin "C") (pinfunction "C_C") (pintype "passive"))
      (node (ref "R4") (pin "1") (pinfunction "1_1") (pintype "passive"))
    )
    (net (code "49") (name "Net-(LED3-PadC)") (class "Default")
      (node (ref "LED3") (pin "C") (pinfunction "C_C") (pintype "passive"))
      (node (ref "R5") (pin "1") (pinfunction "1_1") (pintype "passive"))
    )
    (net (code "50") (name "Net-(LED4-PadC)") (class "Default")
      (node (ref "LED4") (pin "C") (pinfunction "C_C") (pintype "passive"))
      (node (ref "R6") (pin "1") (pinfunction "1_1") (pintype "passive"))
    )
    (net (code "51") (name "Net-(LED5-PadC)") (class "Default")
      (node (ref "LED5") (pin "C") (pinfunction "C_C") (pintype "passive"))
      (node (ref "R7") (pin "1") (pinfunction "1_1") (pintype "passive"))
    )
    (net (code "52") (name "Net-(LED6-PadC)") (class "Default")
      (node (ref "LED6") (pin "C") (pinfunction "C_C") (pintype "passive"))
      (node (ref "R8") (pin "1") (pinfunction "1_1") (pintype "passive"))
    )
    (net (code "53") (name "Net-(U1-A1_PB08(AIN2{slash}SER4:0{slash}TC4:0))") (class "Default")
      (node (ref "R12") (pin "2") (pinfunction "2_2") (pintype "passive"))
      (node (ref "U1") (pin "7") (pinfunction "A1_PB08(AIN2/SER4:0/TC4:0)_7") (pintype "bidirectional"))
    )
    (net (code "54") (name "Net-(U1-A3_PA04(AIN4{slash}REFB{slash}SER0:0{slash}TC0:0))") (class "Default")
      (node (ref "R10") (pin "2") (pinfunction "2_2") (pintype "passive"))
      (node (ref "U1") (pin "9") (pinfunction "A3_PA04(AIN4/REFB/SER0:0/TC0:0)_9") (pintype "bidirectional"))
    )
    (net (code "55") (name "Net-(U1-D8_PA06(AIN6{slash}SER0:2{slash}TC1:0))") (class "Default")
      (node (ref "R11") (pin "2") (pinfunction "2_2") (pintype "passive"))
      (node (ref "U1") (pin "11") (pinfunction "D8_PA06(AIN6/SER0:2/TC1:0)_11") (pintype "bidirectional"))
    )
    (net (code "56") (name "Net-(U1-PA00(XIN32{slash}SER1:0{slash}TC2:0))") (class "Default")
      (node (ref "C1") (pin "2") (pinfunction "2_2") (pintype "passive"))
      (node (ref "U1") (pin "1") (pinfunction "PA00(XIN32/SER1:0/TC2:0)_1") (pintype "bidirectional"))
      (node (ref "Y1") (pin "P$2") (pinfunction "2_P$2") (pintype "passive"))
    )
    (net (code "57") (name "Net-(U1-PA01(XOUT32{slash}SER1:1{slash}TC2:1))") (class "Default")
      (node (ref "C2") (pin "2") (pinfunction "2_2") (pintype "passive"))
      (node (ref "U1") (pin "2") (pinfunction "PA01(XOUT32/SER1:1/TC2:1)_2") (pintype "bidirectional"))
      (node (ref "Y1") (pin "P$1") (pinfunction "1_P$1") (pintype "passive"))
    )
    (net (code "58") (name "Net-(U1-PA15(XOUT{slash}SER2:3+)_D5)") (class "Default")
      (node (ref "R13") (pin "1") (pinfunction "1_1") (pintype "passive"))
      (node (ref "U1") (pin "24") (pinfunction "PA15(XOUT/SER2:3+)_D5_24") (pintype "bidirectional"))
    )
    (net (code "59") (name "Net-(U1-PA21(SER5:3+)_D7)") (class "Default")
      (node (ref "R9") (pin "2") (pinfunction "2_2") (pintype "passive"))
      (node (ref "U1") (pin "30") (pinfunction "PA21(SER5:3+)_D7_30") (pintype "bidirectional"))
    )
    (net (code "60") (name "Net-(U2-~{CS})") (class "Default")
      (node (ref "R22") (pin "1") (pinfunction "1_1") (pintype "passive"))
      (node (ref "U2") (pin "2") (pinfunction "~{CS}_2") (pintype "bidirectional"))
    )
    (net (code "61") (name "Net-(U4-~{CS}{slash}MODE)") (class "Default")
      (node (ref "R26") (pin "2") (pinfunction "2_2") (pintype "passive"))
      (node (ref "U4") (pin "8") (pinfunction "~{CS}/MODE_8") (pintype "bidirectional"))
    )
    (net (code "62") (name "Net-(U5-D)") (class "Default")
      (node (ref "LS1") (pin "N") (pinfunction "N_N") (pintype "passive"))
      (node (ref "U5") (pin "3") (pinfunction "D_3") (pintype "output"))
    )
    (net (code "63") (name "Net-(U5-G)") (class "Default")
      (node (ref "R18") (pin "2") (pinfunction "2_2") (pintype "passive"))
      (node (ref "R19") (pin "1") (pinfunction "1_1") (pintype "passive"))
      (node (ref "U5") (pin "1") (pinfunction "G_1") (pintype "power_in"))
    )
    (net (code "64") (name "unconnected-(AP2112K_3.3V-NC-Pad4)") (class "Default")
      (node (ref "AP2112K_3.3V") (pin "4") (pinfunction "NC_4") (pintype "no_connect"))
    )
    (net (code "65") (name "unconnected-(U1-A2_PB09(AIN3{slash}SER4:1{slash}TC4:1)-Pad8)") (class "Default")
      (node (ref "U1") (pin "8") (pinfunction "A2_PB09(AIN3/SER4:1/TC4:1)_8") (pintype "bidirectional"))
    )
    (net (code "66") (name "unconnected-(U4-ADC1-Pad16)") (class "Default")
      (node (ref "U4") (pin "16") (pinfunction "ADC1_16") (pintype "bidirectional"))
    )
    (net (code "67") (name "unconnected-(U4-ADC2-Pad15)") (class "Default")
      (node (ref "U4") (pin "15") (pinfunction "ADC2_15") (pintype "bidirectional"))
    )
    (net (code "68") (name "unconnected-(U4-ADC3-Pad13)") (class "Default")
      (node (ref "U4") (pin "13") (pinfunction "ADC3_13") (pintype "bidirectional"))
    )
    (net (code "69") (name "unconnected-(U4-INT1-Pad11)") (class "Default")
      (node (ref "U4") (pin "11") (pinfunction "INT1_11") (pintype "bidirectional"))
    )
  )
)
